# plugV8-Relay-NO.net
KiCad netlist of a schematic drawn in EAGLE
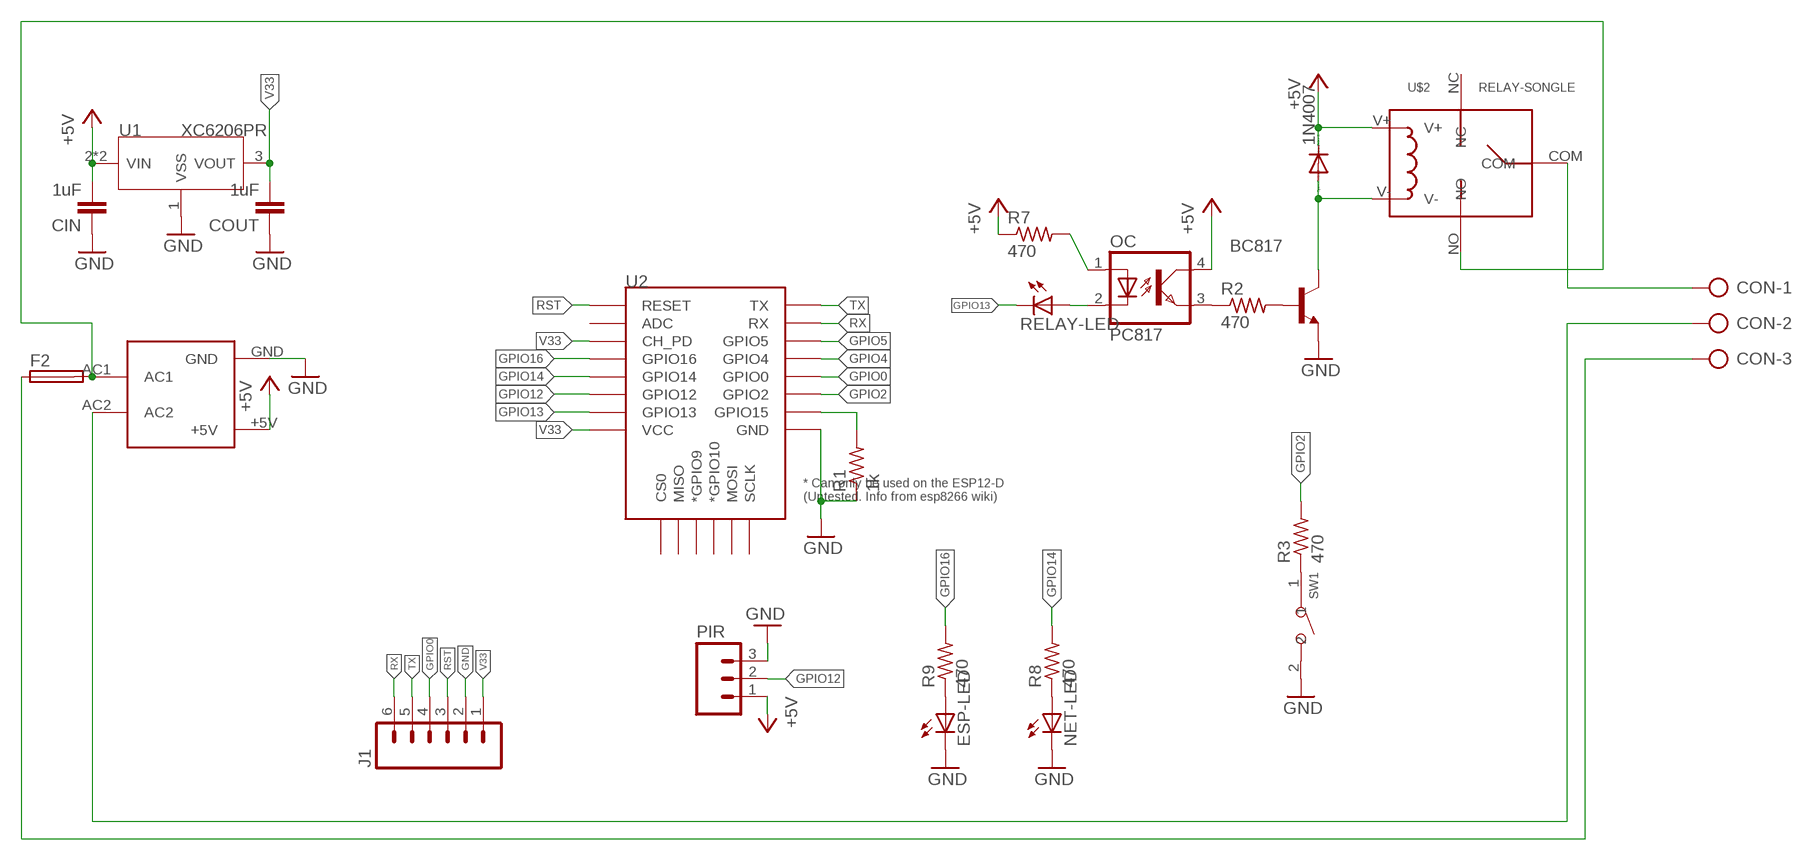
[diagram p0: schematic, sheet 1]

(export (version "E")
  (design (tool "Eeschema 10.0.6"))
  (components
    (comp (ref "1N4007")
      (value "CGRM4007-G")
      (footprint "eagle-import:SOD-123_MINI-SMA")
      (libsource (lib "eagle-import") (part "CGRM400-G7"))
    )
    (comp (ref "BC817")
      (value "BC817-NPN-SOT23-BEC")
      (footprint "eagle-import:SOT23-BEC")
      (libsource (lib "eagle-import") (part "-NPN-SOT23-BECBC817"))
    )
    (comp (ref "CIN")
      (value "1uF")
      (footprint "eagle-import:C0805")
      (libsource (lib "eagle-import") (part "C-EUC0805"))
    )
    (comp (ref "CON")
      (value "AK300/3")
      (footprint "eagle-import:AK300_3")
      (libsource (lib "eagle-import") (part "AK300/3"))
    )
    (comp (ref "COUT")
      (value "1uF")
      (footprint "eagle-import:C0805")
      (libsource (lib "eagle-import") (part "C-EUC0805"))
    )
    (comp (ref "ESP-LED")
      (value "LED3MM")
      (footprint "eagle-import:LED3MM")
      (libsource (lib "eagle-import") (part "LED3MM"))
    )
    (comp (ref "F2")
      (value "TR5")
      (footprint "eagle-import:TR5")
      (libsource (lib "eagle-import") (part "TR5"))
    )
    (comp (ref "J1")
      (value "M06SILK_FEMALE_PTH")
      (footprint "eagle-import:1X06")
      (libsource (lib "eagle-import") (part "M06SILK_FEMALE_PTH"))
    )
    (comp (ref "NET-LED")
      (value "LED3MM")
      (footprint "eagle-import:LED3MM")
      (libsource (lib "eagle-import") (part "LED3MM"))
    )
    (comp (ref "OC")
      (value "PC817")
      (footprint "eagle-import:DIL04")
      (fields (field (name "MPN") "PC817X4J000F"))
      (libsource (lib "eagle-import") (part "PC817"))
    )
    (comp (ref "PIR")
      (value "M03POLAR")
      (footprint "eagle-import:MOLEX-1X3")
      (libsource (lib "eagle-import") (part "M03POLAR"))
    )
    (comp (ref "R1")
      (value "1k")
      (footprint "eagle-import:0204V")
      (libsource (lib "eagle-import") (part "R-US_0204/2V"))
    )
    (comp (ref "R2")
      (value "470")
      (footprint "eagle-import:0204V")
      (libsource (lib "eagle-import") (part "R-US_0204/2V"))
    )
    (comp (ref "R3")
      (value "470")
      (footprint "eagle-import:0204V")
      (libsource (lib "eagle-import") (part "R-US_0204/2V"))
    )
    (comp (ref "R7")
      (value "470")
      (footprint "eagle-import:0204V")
      (libsource (lib "eagle-import") (part "R-US_0204/2V"))
    )
    (comp (ref "R8")
      (value "470")
      (footprint "eagle-import:0204V")
      (libsource (lib "eagle-import") (part "R-US_0204/2V"))
    )
    (comp (ref "R9")
      (value "470")
      (footprint "eagle-import:0204V")
      (libsource (lib "eagle-import") (part "R-US_0204/2V"))
    )
    (comp (ref "RELAY-LED")
      (value "LED3MM")
      (footprint "eagle-import:LED3MM")
      (libsource (lib "eagle-import") (part "LED3MM"))
    )
    (comp (ref "SW1")
      (value "DIP-BUTTON(2P-6.0X3.0X4.3MM)-TS-1101F")
      (footprint "eagle-import:SW2-5.0-6.0X3.0X4.3MM")
      (libsource (lib "eagle-import") (part "DIP-BUTTON(2P-6.0X3.0X4.3MM)-TS-1101F"))
    )
    (comp (ref "U$1")
      (value "HLK-PM01")
      (footprint "eagle-import:HLK-PM01")
      (libsource (lib "eagle-import") (part "HLK-PM01"))
    )
    (comp (ref "U$2")
      (value "RELAY-SONGLE")
      (footprint "eagle-import:RELAY-SONGLE")
      (libsource (lib "eagle-import") (part "RELAY-SONGLE"))
    )
    (comp (ref "U1")
      (value "XC6206PR")
      (footprint "eagle-import:SOT89")
      (libsource (lib "eagle-import") (part "XC6206PR"))
    )
    (comp (ref "U2")
      (value "ESP12ESMD")
      (footprint "eagle-import:ESP12E-SMD")
      (libsource (lib "eagle-import") (part "ESP12ESMD"))
    )
  )
  (nets
    (net (code "1") (name "+5V") (class "Default")
      (node (ref "1N4007") (pin "C") (pinfunction "C_C") (pintype "passive"))
      (node (ref "CIN") (pin "2") (pinfunction "2_2") (pintype "passive"))
      (node (ref "OC") (pin "4") (pinfunction "COL_4") (pintype "passive"))
      (node (ref "PIR") (pin "1") (pinfunction "1_1") (pintype "passive"))
      (node (ref "R7") (pin "1") (pinfunction "1_1") (pintype "passive"))
      (node (ref "U$1") (pin "+5V") (pinfunction "+5V_+5V") (pintype "bidirectional"))
      (node (ref "U$2") (pin "V+") (pinfunction "V+_V+") (pintype "bidirectional"))
      (node (ref "U1") (pin "2") (pinfunction "VIN_2") (pintype "input"))
      (node (ref "U1") (pin "4") (pinfunction "VIN_4") (pintype "input"))
    )
    (net (code "2") (name "GND") (class "Default")
      (node (ref "BC817") (pin "E") (pinfunction "E_E") (pintype "passive"))
      (node (ref "CIN") (pin "1") (pinfunction "1_1") (pintype "passive"))
      (node (ref "COUT") (pin "1") (pinfunction "1_1") (pintype "passive"))
      (node (ref "ESP-LED") (pin "K") (pinfunction "C_K") (pintype "passive"))
      (node (ref "J1") (pin "2") (pinfunction "2_2") (pintype "passive"))
      (node (ref "NET-LED") (pin "K") (pinfunction "C_K") (pintype "passive"))
      (node (ref "PIR") (pin "3") (pinfunction "3_3") (pintype "passive"))
      (node (ref "R1") (pin "1") (pinfunction "1_1") (pintype "passive"))
      (node (ref "SW1") (pin "2") (pinfunction "2_2") (pintype "bidirectional"))
      (node (ref "U$1") (pin "GND") (pinfunction "GND_GND") (pintype "bidirectional"))
      (node (ref "U1") (pin "1") (pinfunction "VSS_1") (pintype "power_in"))
      (node (ref "U2") (pin "GND") (pinfunction "GND_GND") (pintype "bidirectional"))
    )
    (net (code "3") (name "GPIO0") (class "Default")
      (node (ref "J1") (pin "4") (pinfunction "4_4") (pintype "passive"))
      (node (ref "U2") (pin "GPIO0") (pinfunction "GPIO0_GPIO0") (pintype "bidirectional"))
    )
    (net (code "4") (name "GPIO2") (class "Default")
      (node (ref "R3") (pin "2") (pinfunction "2_2") (pintype "passive"))
      (node (ref "U2") (pin "GPIO2") (pinfunction "GPIO2_GPIO2") (pintype "bidirectional"))
    )
    (net (code "5") (name "GPIO4") (class "Default")
      (node (ref "U2") (pin "GPIO4") (pinfunction "GPIO4_GPIO4") (pintype "bidirectional"))
    )
    (net (code "6") (name "GPIO5") (class "Default")
      (node (ref "U2") (pin "GPIO5") (pinfunction "GPIO5_GPIO5") (pintype "bidirectional"))
    )
    (net (code "7") (name "GPIO12") (class "Default")
      (node (ref "PIR") (pin "2") (pinfunction "2_2") (pintype "passive"))
      (node (ref "U2") (pin "GPIO12") (pinfunction "GPIO12_GPIO12") (pintype "bidirectional"))
    )
    (net (code "8") (name "GPIO13") (class "Default")
      (node (ref "RELAY-LED") (pin "K") (pinfunction "C_K") (pintype "passive"))
      (node (ref "U2") (pin "GPIO13") (pinfunction "GPIO13_GPIO13") (pintype "bidirectional"))
    )
    (net (code "9") (name "GPIO14") (class "Default")
      (node (ref "R8") (pin "2") (pinfunction "2_2") (pintype "passive"))
      (node (ref "U2") (pin "GPIO14") (pinfunction "GPIO14_GPIO14") (pintype "bidirectional"))
    )
    (net (code "10") (name "GPIO16") (class "Default")
      (node (ref "R9") (pin "2") (pinfunction "2_2") (pintype "passive"))
      (node (ref "U2") (pin "GPIO16") (pinfunction "GPIO16_GPIO16") (pintype "bidirectional"))
    )
    (net (code "11") (name "Net-(1N4007-PadA)") (class "Default")
      (node (ref "1N4007") (pin "A") (pinfunction "A_A") (pintype "passive"))
      (node (ref "BC817") (pin "C") (pinfunction "C_C") (pintype "passive"))
      (node (ref "U$2") (pin "V-") (pinfunction "V-_V-") (pintype "bidirectional"))
    )
    (net (code "12") (name "Net-(BC817-PadB)") (class "Default")
      (node (ref "BC817") (pin "B") (pinfunction "B_B") (pintype "passive"))
      (node (ref "R2") (pin "2") (pinfunction "2_2") (pintype "passive"))
    )
    (net (code "13") (name "Net-(CONA-KL)") (class "Default")
      (node (ref "CON") (pin "1") (pinfunction "KL_1") (pintype "passive"))
      (node (ref "U$2") (pin "COM") (pinfunction "COM_COM") (pintype "bidirectional"))
    )
    (net (code "14") (name "Net-(CONB-KL)") (class "Default")
      (node (ref "CON") (pin "2") (pinfunction "KL_2") (pintype "passive"))
      (node (ref "U$1") (pin "AC2") (pinfunction "AC2_AC2") (pintype "bidirectional"))
    )
    (net (code "15") (name "Net-(CONC-KL)") (class "Default")
      (node (ref "CON") (pin "3") (pinfunction "KL_3") (pintype "passive"))
      (node (ref "F2") (pin "1") (pinfunction "1_1") (pintype "passive"))
    )
    (net (code "16") (name "Net-(ESP-LED-PadA)") (class "Default")
      (node (ref "ESP-LED") (pin "A") (pinfunction "A_A") (pintype "passive"))
      (node (ref "R9") (pin "1") (pinfunction "1_1") (pintype "passive"))
    )
    (net (code "17") (name "Net-(F2-Pad2)") (class "Default")
      (node (ref "F2") (pin "2") (pinfunction "2_2") (pintype "passive"))
      (node (ref "U$1") (pin "AC1") (pinfunction "AC1_AC1") (pintype "bidirectional"))
      (node (ref "U$2") (pin "NO") (pinfunction "NO_NO") (pintype "bidirectional"))
    )
    (net (code "18") (name "Net-(NET-LED-PadA)") (class "Default")
      (node (ref "NET-LED") (pin "A") (pinfunction "A_A") (pintype "passive"))
      (node (ref "R8") (pin "1") (pinfunction "1_1") (pintype "passive"))
    )
    (net (code "19") (name "Net-(OC-A)") (class "Default")
      (node (ref "OC") (pin "1") (pinfunction "A_1") (pintype "passive"))
      (node (ref "R7") (pin "2") (pinfunction "2_2") (pintype "passive"))
    )
    (net (code "20") (name "Net-(OC-C)") (class "Default")
      (node (ref "OC") (pin "2") (pinfunction "C_2") (pintype "passive"))
      (node (ref "RELAY-LED") (pin "A") (pinfunction "A_A") (pintype "passive"))
    )
    (net (code "21") (name "Net-(OC-EMIT)") (class "Default")
      (node (ref "OC") (pin "3") (pinfunction "EMIT_3") (pintype "passive"))
      (node (ref "R2") (pin "1") (pinfunction "1_1") (pintype "passive"))
    )
    (net (code "22") (name "Net-(R1-Pad2)") (class "Default")
      (node (ref "R1") (pin "2") (pinfunction "2_2") (pintype "passive"))
      (node (ref "U2") (pin "GPIO15") (pinfunction "GPIO15_GPIO15") (pintype "bidirectional"))
    )
    (net (code "23") (name "Net-(R3-Pad1)") (class "Default")
      (node (ref "R3") (pin "1") (pinfunction "1_1") (pintype "passive"))
      (node (ref "SW1") (pin "1") (pinfunction "1_1") (pintype "bidirectional"))
    )
    (net (code "24") (name "RST") (class "Default")
      (node (ref "J1") (pin "3") (pinfunction "3_3") (pintype "passive"))
      (node (ref "U2") (pin "RESET") (pinfunction "RESET_RESET") (pintype "bidirectional"))
    )
    (net (code "25") (name "RX") (class "Default")
      (node (ref "J1") (pin "6") (pinfunction "6_6") (pintype "passive"))
      (node (ref "U2") (pin "RXD0") (pinfunction "RX_RXD0") (pintype "bidirectional"))
    )
    (net (code "26") (name "TX") (class "Default")
      (node (ref "J1") (pin "5") (pinfunction "5_5") (pintype "passive"))
      (node (ref "U2") (pin "TXD0") (pinfunction "TX_TXD0") (pintype "bidirectional"))
    )
    (net (code "27") (name "V33") (class "Default")
      (node (ref "COUT") (pin "2") (pinfunction "2_2") (pintype "passive"))
      (node (ref "J1") (pin "1") (pinfunction "1_1") (pintype "passive"))
      (node (ref "U1") (pin "3") (pinfunction "VOUT_3") (pintype "output"))
      (node (ref "U2") (pin "CH_PD") (pinfunction "CH_PD_CH_PD") (pintype "bidirectional"))
      (node (ref "U2") (pin "VCC") (pinfunction "VCC_VCC") (pintype "bidirectional"))
    )
    (net (code "28") (name "unconnected-(U$2-PadNC)") (class "Default")
      (node (ref "U$2") (pin "NC") (pinfunction "NC_NC") (pintype "bidirectional"))
    )
    (net (code "29") (name "unconnected-(U2-*GPIO9-PadGPIO9)") (class "Default")
      (node (ref "U2") (pin "GPIO9") (pinfunction "*GPIO9_GPIO9") (pintype "bidirectional"))
    )
    (net (code "30") (name "unconnected-(U2-*GPIO10-PadGPIO10)") (class "Default")
      (node (ref "U2") (pin "GPIO10") (pinfunction "*GPIO10_GPIO10") (pintype "bidirectional"))
    )
    (net (code "31") (name "unconnected-(U2-PadADC)") (class "Default")
      (node (ref "U2") (pin "ADC") (pinfunction "ADC_ADC") (pintype "bidirectional"))
    )
    (net (code "32") (name "unconnected-(U2-PadCS0)") (class "Default")
      (node (ref "U2") (pin "CS0") (pinfunction "CS0_CS0") (pintype "bidirectional"))
    )
    (net (code "33") (name "unconnected-(U2-PadMISO)") (class "Default")
      (node (ref "U2") (pin "MISO") (pinfunction "MISO_MISO") (pintype "bidirectional"))
    )
    (net (code "34") (name "unconnected-(U2-PadMOSI)") (class "Default")
      (node (ref "U2") (pin "MOSI") (pinfunction "MOSI_MOSI") (pintype "bidirectional"))
    )
    (net (code "35") (name "unconnected-(U2-PadSCLK)") (class "Default")
      (node (ref "U2") (pin "SCLK") (pinfunction "SCLK_SCLK") (pintype "bidirectional"))
    )
  )
)
